# spotmicroservo.net
KiCad netlist of a schematic drawn in EAGLE
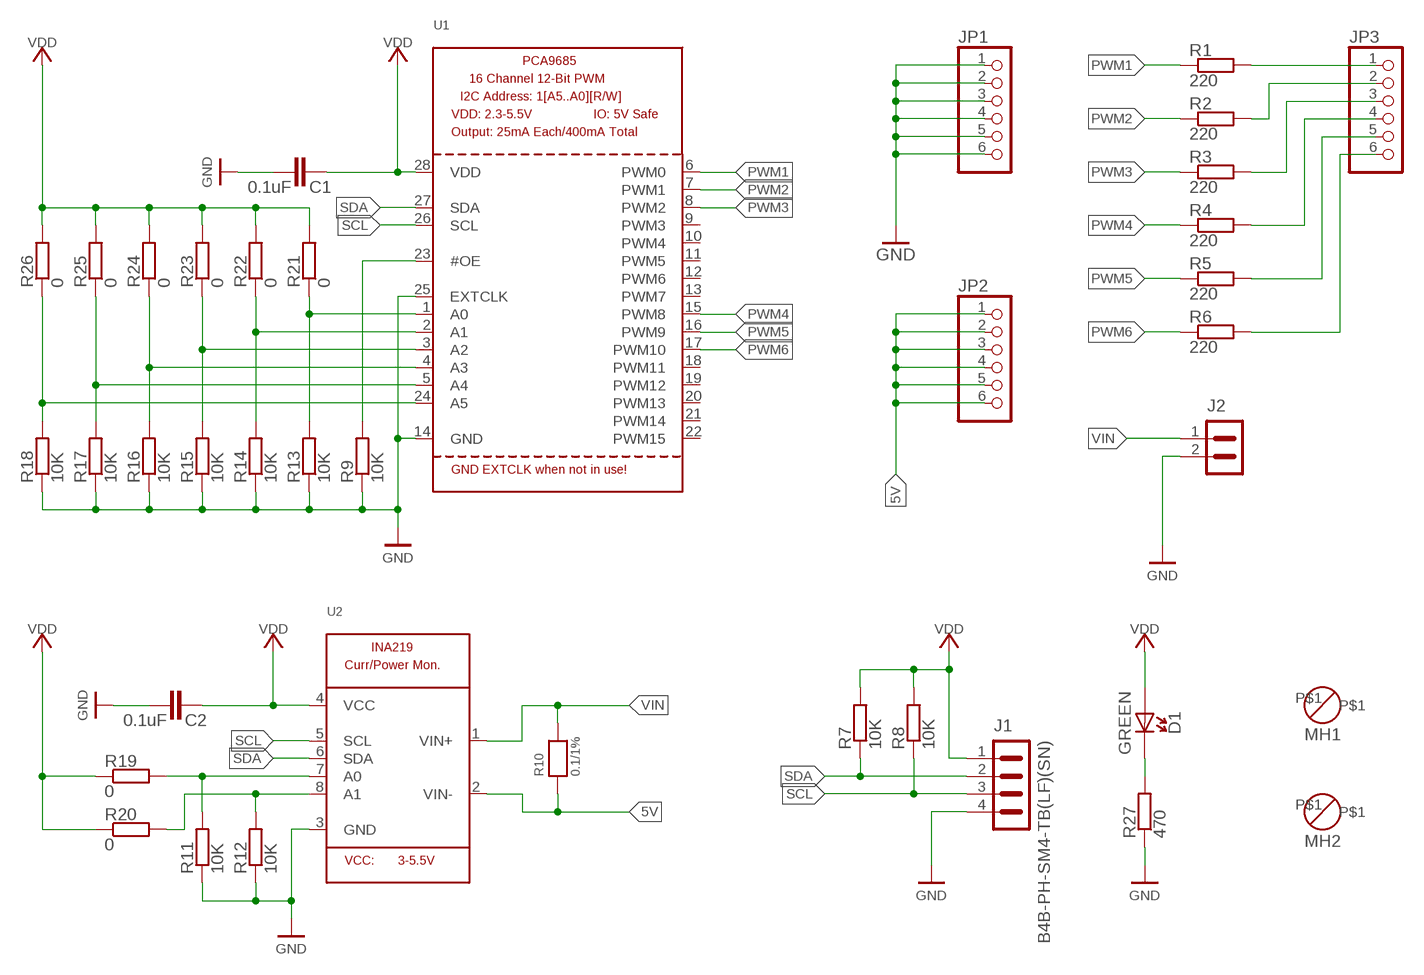
[diagram p0: schematic, sheet 1]

(export (version "E")
  (design (tool "Eeschema 10.0.6"))
  (components
    (comp (ref "C1")
      (value "0.1uF")
      (footprint "eagle-import:C0402")
      (libsource (lib "eagle-import") (part "CAPACITOR_NPOL-0402"))
    )
    (comp (ref "C2")
      (value "0.1uF")
      (footprint "eagle-import:C0402")
      (libsource (lib "eagle-import") (part "CAPACITOR_NPOL-0402"))
    )
    (comp (ref "D1")
      (value "GREEN")
      (footprint "eagle-import:D0402")
      (libsource (lib "eagle-import") (part "LED_SINGLE-0402"))
    )
    (comp (ref "J1")
      (value "B4B-PH-SM4-TB(LF)(SN)")
      (footprint "eagle-import:CON_JST_B4B-PH-SM4-TB(LF)(SN)")
      (libsource (lib "eagle-import") (part "CON_HEADER_1X04_JST_B4B-PH-SM4-TB(LF)(SN)"))
    )
    (comp (ref "J2")
      (value "CON_HEADER_1X02-B2B-XH-A(LF)(SN)")
      (footprint "eagle-import:JST_B2B-XH-A(LF)(SN)")
      (libsource (lib "eagle-import") (part "CON_HEADER_1X02-B2B-XH-A(LF)(SN)"))
    )
    (comp (ref "JP1")
      (value "PINHD-1X6B")
      (footprint "eagle-import:1X06-BIG")
      (libsource (lib "eagle-import") (part "PINHD-1X6B"))
    )
    (comp (ref "JP2")
      (value "PINHD-1X6B")
      (footprint "eagle-import:1X06-BIG")
      (libsource (lib "eagle-import") (part "PINHD-1X6B"))
    )
    (comp (ref "JP3")
      (value "PINHD-1X6B")
      (footprint "eagle-import:1X06-BIG")
      (libsource (lib "eagle-import") (part "PINHD-1X6B"))
    )
    (comp (ref "MH1")
      (value "MOUNT-HOLE2.6MM")
      (footprint "eagle-import:MOUNT-HOLE2.6")
      (libsource (lib "eagle-import") (part "MOUNT-HOLE2.6MM"))
    )
    (comp (ref "MH2")
      (value "MOUNT-HOLE2.6MM")
      (footprint "eagle-import:MOUNT-HOLE2.6")
      (libsource (lib "eagle-import") (part "MOUNT-HOLE2.6MM"))
    )
    (comp (ref "R1")
      (value "220")
      (footprint "eagle-import:R0402")
      (libsource (lib "eagle-import") (part "RESISTOR-0402"))
    )
    (comp (ref "R2")
      (value "220")
      (footprint "eagle-import:R0402")
      (libsource (lib "eagle-import") (part "RESISTOR-0402"))
    )
    (comp (ref "R3")
      (value "220")
      (footprint "eagle-import:R0402")
      (libsource (lib "eagle-import") (part "RESISTOR-0402"))
    )
    (comp (ref "R4")
      (value "220")
      (footprint "eagle-import:R0402")
      (libsource (lib "eagle-import") (part "RESISTOR-0402"))
    )
    (comp (ref "R5")
      (value "220")
      (footprint "eagle-import:R0402")
      (libsource (lib "eagle-import") (part "RESISTOR-0402"))
    )
    (comp (ref "R6")
      (value "220")
      (footprint "eagle-import:R0402")
      (libsource (lib "eagle-import") (part "RESISTOR-0402"))
    )
    (comp (ref "R7")
      (value "10K")
      (footprint "eagle-import:R0402")
      (libsource (lib "eagle-import") (part "RESISTOR-0402"))
    )
    (comp (ref "R8")
      (value "10K")
      (footprint "eagle-import:R0402")
      (libsource (lib "eagle-import") (part "RESISTOR-0402"))
    )
    (comp (ref "R9")
      (value "10K")
      (footprint "eagle-import:R0402")
      (libsource (lib "eagle-import") (part "RESISTOR-0402"))
    )
    (comp (ref "R10")
      (value "0.1/1%")
      (footprint "eagle-import:MICROBUILDER_2512")
      (libsource (lib "eagle-import") (part "MICROBUILDER_RESISTOR2512"))
    )
    (comp (ref "R11")
      (value "10K")
      (footprint "eagle-import:R0402")
      (libsource (lib "eagle-import") (part "RESISTOR-0402"))
    )
    (comp (ref "R12")
      (value "10K")
      (footprint "eagle-import:R0402")
      (libsource (lib "eagle-import") (part "RESISTOR-0402"))
    )
    (comp (ref "R13")
      (value "10K")
      (footprint "eagle-import:R0402")
      (libsource (lib "eagle-import") (part "RESISTOR-0402"))
    )
    (comp (ref "R14")
      (value "10K")
      (footprint "eagle-import:R0402")
      (libsource (lib "eagle-import") (part "RESISTOR-0402"))
    )
    (comp (ref "R15")
      (value "10K")
      (footprint "eagle-import:R0402")
      (libsource (lib "eagle-import") (part "RESISTOR-0402"))
    )
    (comp (ref "R16")
      (value "10K")
      (footprint "eagle-import:R0402")
      (libsource (lib "eagle-import") (part "RESISTOR-0402"))
    )
    (comp (ref "R17")
      (value "10K")
      (footprint "eagle-import:R0402")
      (libsource (lib "eagle-import") (part "RESISTOR-0402"))
    )
    (comp (ref "R18")
      (value "10K")
      (footprint "eagle-import:R0402")
      (libsource (lib "eagle-import") (part "RESISTOR-0402"))
    )
    (comp (ref "R19")
      (value "0")
      (footprint "eagle-import:R0402")
      (libsource (lib "eagle-import") (part "RESISTOR-0402"))
    )
    (comp (ref "R20")
      (value "0")
      (footprint "eagle-import:R0402")
      (libsource (lib "eagle-import") (part "RESISTOR-0402"))
    )
    (comp (ref "R21")
      (value "0")
      (footprint "eagle-import:R0402")
      (libsource (lib "eagle-import") (part "RESISTOR-0402"))
    )
    (comp (ref "R22")
      (value "0")
      (footprint "eagle-import:R0402")
      (libsource (lib "eagle-import") (part "RESISTOR-0402"))
    )
    (comp (ref "R23")
      (value "0")
      (footprint "eagle-import:R0402")
      (libsource (lib "eagle-import") (part "RESISTOR-0402"))
    )
    (comp (ref "R24")
      (value "0")
      (footprint "eagle-import:R0402")
      (libsource (lib "eagle-import") (part "RESISTOR-0402"))
    )
    (comp (ref "R25")
      (value "0")
      (footprint "eagle-import:R0402")
      (libsource (lib "eagle-import") (part "RESISTOR-0402"))
    )
    (comp (ref "R26")
      (value "0")
      (footprint "eagle-import:R0402")
      (libsource (lib "eagle-import") (part "RESISTOR-0402"))
    )
    (comp (ref "R27")
      (value "470")
      (footprint "eagle-import:R0402")
      (libsource (lib "eagle-import") (part "RESISTOR-0402"))
    )
    (comp (ref "U1")
      (value "PCA9685")
      (footprint "eagle-import:TSSOP28")
      (libsource (lib "eagle-import") (part "PCA9685"))
    )
    (comp (ref "U2")
      (value "MICROBUILDER_INA219")
      (footprint "eagle-import:MICROBUILDER_SOT23-8")
      (libsource (lib "eagle-import") (part "MICROBUILDER_INA219"))
    )
  )
  (nets
    (net (code "1") (name "5V") (class "Default")
      (node (ref "JP2") (pin "1") (pinfunction "1_1") (pintype "passive"))
      (node (ref "JP2") (pin "2") (pinfunction "2_2") (pintype "passive"))
      (node (ref "JP2") (pin "3") (pinfunction "3_3") (pintype "passive"))
      (node (ref "JP2") (pin "4") (pinfunction "4_4") (pintype "passive"))
      (node (ref "JP2") (pin "5") (pinfunction "5_5") (pintype "passive"))
      (node (ref "JP2") (pin "6") (pinfunction "6_6") (pintype "passive"))
      (node (ref "R10") (pin "1") (pinfunction "1_1") (pintype "passive"))
      (node (ref "U2") (pin "2") (pinfunction "VIN-_2") (pintype "bidirectional"))
    )
    (net (code "2") (name "GND") (class "Default")
      (node (ref "C1") (pin "1") (pinfunction "1_1") (pintype "passive"))
      (node (ref "C2") (pin "1") (pinfunction "1_1") (pintype "passive"))
      (node (ref "J1") (pin "4") (pinfunction "4_4") (pintype "bidirectional"))
      (node (ref "J2") (pin "2") (pinfunction "2_2") (pintype "passive"))
      (node (ref "JP1") (pin "1") (pinfunction "1_1") (pintype "passive"))
      (node (ref "JP1") (pin "2") (pinfunction "2_2") (pintype "passive"))
      (node (ref "JP1") (pin "3") (pinfunction "3_3") (pintype "passive"))
      (node (ref "JP1") (pin "4") (pinfunction "4_4") (pintype "passive"))
      (node (ref "JP1") (pin "5") (pinfunction "5_5") (pintype "passive"))
      (node (ref "JP1") (pin "6") (pinfunction "6_6") (pintype "passive"))
      (node (ref "R11") (pin "1") (pinfunction "1_1") (pintype "passive"))
      (node (ref "R12") (pin "1") (pinfunction "1_1") (pintype "passive"))
      (node (ref "R13") (pin "1") (pinfunction "1_1") (pintype "passive"))
      (node (ref "R14") (pin "1") (pinfunction "1_1") (pintype "passive"))
      (node (ref "R15") (pin "1") (pinfunction "1_1") (pintype "passive"))
      (node (ref "R16") (pin "1") (pinfunction "1_1") (pintype "passive"))
      (node (ref "R17") (pin "1") (pinfunction "1_1") (pintype "passive"))
      (node (ref "R18") (pin "1") (pinfunction "1_1") (pintype "passive"))
      (node (ref "R27") (pin "1") (pinfunction "1_1") (pintype "passive"))
      (node (ref "R9") (pin "1") (pinfunction "1_1") (pintype "passive"))
      (node (ref "U1") (pin "14") (pinfunction "GND_14") (pintype "power_in"))
      (node (ref "U1") (pin "25") (pinfunction "EXTCLK_25") (pintype "input"))
      (node (ref "U2") (pin "3") (pinfunction "GND_3") (pintype "bidirectional"))
    )
    (net (code "3") (name "Net-(D1-C)") (class "Default")
      (node (ref "D1") (pin "2") (pinfunction "C_2") (pintype "passive"))
      (node (ref "R27") (pin "2") (pinfunction "2_2") (pintype "passive"))
    )
    (net (code "4") (name "Net-(JP3-Pad1)") (class "Default")
      (node (ref "JP3") (pin "1") (pinfunction "1_1") (pintype "passive"))
      (node (ref "R1") (pin "2") (pinfunction "2_2") (pintype "passive"))
    )
    (net (code "5") (name "Net-(JP3-Pad2)") (class "Default")
      (node (ref "JP3") (pin "2") (pinfunction "2_2") (pintype "passive"))
      (node (ref "R2") (pin "2") (pinfunction "2_2") (pintype "passive"))
    )
    (net (code "6") (name "Net-(JP3-Pad3)") (class "Default")
      (node (ref "JP3") (pin "3") (pinfunction "3_3") (pintype "passive"))
      (node (ref "R3") (pin "2") (pinfunction "2_2") (pintype "passive"))
    )
    (net (code "7") (name "Net-(JP3-Pad4)") (class "Default")
      (node (ref "JP3") (pin "4") (pinfunction "4_4") (pintype "passive"))
      (node (ref "R4") (pin "2") (pinfunction "2_2") (pintype "passive"))
    )
    (net (code "8") (name "Net-(JP3-Pad5)") (class "Default")
      (node (ref "JP3") (pin "5") (pinfunction "5_5") (pintype "passive"))
      (node (ref "R5") (pin "2") (pinfunction "2_2") (pintype "passive"))
    )
    (net (code "9") (name "Net-(JP3-Pad6)") (class "Default")
      (node (ref "JP3") (pin "6") (pinfunction "6_6") (pintype "passive"))
      (node (ref "R6") (pin "2") (pinfunction "2_2") (pintype "passive"))
    )
    (net (code "10") (name "Net-(U1-#OE)") (class "Default")
      (node (ref "R9") (pin "2") (pinfunction "2_2") (pintype "passive"))
      (node (ref "U1") (pin "23") (pinfunction "#OE_23") (pintype "input"))
    )
    (net (code "11") (name "Net-(U1-A0)") (class "Default")
      (node (ref "R13") (pin "2") (pinfunction "2_2") (pintype "passive"))
      (node (ref "R21") (pin "1") (pinfunction "1_1") (pintype "passive"))
      (node (ref "U1") (pin "1") (pinfunction "A0_1") (pintype "bidirectional"))
    )
    (net (code "12") (name "Net-(U1-A1)") (class "Default")
      (node (ref "R14") (pin "2") (pinfunction "2_2") (pintype "passive"))
      (node (ref "R22") (pin "1") (pinfunction "1_1") (pintype "passive"))
      (node (ref "U1") (pin "2") (pinfunction "A1_2") (pintype "bidirectional"))
    )
    (net (code "13") (name "Net-(U1-A2)") (class "Default")
      (node (ref "R15") (pin "2") (pinfunction "2_2") (pintype "passive"))
      (node (ref "R23") (pin "1") (pinfunction "1_1") (pintype "passive"))
      (node (ref "U1") (pin "3") (pinfunction "A2_3") (pintype "bidirectional"))
    )
    (net (code "14") (name "Net-(U1-A3)") (class "Default")
      (node (ref "R16") (pin "2") (pinfunction "2_2") (pintype "passive"))
      (node (ref "R24") (pin "1") (pinfunction "1_1") (pintype "passive"))
      (node (ref "U1") (pin "4") (pinfunction "A3_4") (pintype "bidirectional"))
    )
    (net (code "15") (name "Net-(U1-A4)") (class "Default")
      (node (ref "R17") (pin "2") (pinfunction "2_2") (pintype "passive"))
      (node (ref "R25") (pin "1") (pinfunction "1_1") (pintype "passive"))
      (node (ref "U1") (pin "5") (pinfunction "A4_5") (pintype "bidirectional"))
    )
    (net (code "16") (name "Net-(U1-A5)") (class "Default")
      (node (ref "R18") (pin "2") (pinfunction "2_2") (pintype "passive"))
      (node (ref "R26") (pin "1") (pinfunction "1_1") (pintype "passive"))
      (node (ref "U1") (pin "24") (pinfunction "A5_24") (pintype "bidirectional"))
    )
    (net (code "17") (name "Net-(U2-A0)") (class "Default")
      (node (ref "R11") (pin "2") (pinfunction "2_2") (pintype "passive"))
      (node (ref "R19") (pin "2") (pinfunction "2_2") (pintype "passive"))
      (node (ref "U2") (pin "7") (pinfunction "A0_7") (pintype "bidirectional"))
    )
    (net (code "18") (name "Net-(U2-A1)") (class "Default")
      (node (ref "R12") (pin "2") (pinfunction "2_2") (pintype "passive"))
      (node (ref "R20") (pin "2") (pinfunction "2_2") (pintype "passive"))
      (node (ref "U2") (pin "8") (pinfunction "A1_8") (pintype "bidirectional"))
    )
    (net (code "19") (name "PWM1") (class "Default")
      (node (ref "R1") (pin "1") (pinfunction "1_1") (pintype "passive"))
      (node (ref "U1") (pin "6") (pinfunction "PWM0_6") (pintype "output"))
    )
    (net (code "20") (name "PWM2") (class "Default")
      (node (ref "R2") (pin "1") (pinfunction "1_1") (pintype "passive"))
      (node (ref "U1") (pin "7") (pinfunction "PWM1_7") (pintype "output"))
    )
    (net (code "21") (name "PWM3") (class "Default")
      (node (ref "R3") (pin "1") (pinfunction "1_1") (pintype "passive"))
      (node (ref "U1") (pin "8") (pinfunction "PWM2_8") (pintype "output"))
    )
    (net (code "22") (name "PWM4") (class "Default")
      (node (ref "R4") (pin "1") (pinfunction "1_1") (pintype "passive"))
      (node (ref "U1") (pin "15") (pinfunction "PWM8_15") (pintype "output"))
    )
    (net (code "23") (name "PWM5") (class "Default")
      (node (ref "R5") (pin "1") (pinfunction "1_1") (pintype "passive"))
      (node (ref "U1") (pin "16") (pinfunction "PWM9_16") (pintype "output"))
    )
    (net (code "24") (name "PWM6") (class "Default")
      (node (ref "R6") (pin "1") (pinfunction "1_1") (pintype "passive"))
      (node (ref "U1") (pin "17") (pinfunction "PWM10_17") (pintype "output"))
    )
    (net (code "25") (name "SCL") (class "Default")
      (node (ref "J1") (pin "3") (pinfunction "3_3") (pintype "bidirectional"))
      (node (ref "R8") (pin "1") (pinfunction "1_1") (pintype "passive"))
      (node (ref "U1") (pin "26") (pinfunction "SCL_26") (pintype "bidirectional"))
      (node (ref "U2") (pin "5") (pinfunction "SCL_5") (pintype "bidirectional"))
    )
    (net (code "26") (name "SDA") (class "Default")
      (node (ref "J1") (pin "2") (pinfunction "2_2") (pintype "bidirectional"))
      (node (ref "R7") (pin "1") (pinfunction "1_1") (pintype "passive"))
      (node (ref "U1") (pin "27") (pinfunction "SDA_27") (pintype "bidirectional"))
      (node (ref "U2") (pin "6") (pinfunction "SDA_6") (pintype "bidirectional"))
    )
    (net (code "27") (name "VDD") (class "Default")
      (node (ref "C1") (pin "2") (pinfunction "2_2") (pintype "passive"))
      (node (ref "C2") (pin "2") (pinfunction "2_2") (pintype "passive"))
      (node (ref "D1") (pin "1") (pinfunction "A_1") (pintype "passive"))
      (node (ref "J1") (pin "1") (pinfunction "1_1") (pintype "bidirectional"))
      (node (ref "R19") (pin "1") (pinfunction "1_1") (pintype "passive"))
      (node (ref "R20") (pin "1") (pinfunction "1_1") (pintype "passive"))
      (node (ref "R21") (pin "2") (pinfunction "2_2") (pintype "passive"))
      (node (ref "R22") (pin "2") (pinfunction "2_2") (pintype "passive"))
      (node (ref "R23") (pin "2") (pinfunction "2_2") (pintype "passive"))
      (node (ref "R24") (pin "2") (pinfunction "2_2") (pintype "passive"))
      (node (ref "R25") (pin "2") (pinfunction "2_2") (pintype "passive"))
      (node (ref "R26") (pin "2") (pinfunction "2_2") (pintype "passive"))
      (node (ref "R7") (pin "2") (pinfunction "2_2") (pintype "passive"))
      (node (ref "R8") (pin "2") (pinfunction "2_2") (pintype "passive"))
      (node (ref "U1") (pin "28") (pinfunction "VDD_28") (pintype "power_in"))
      (node (ref "U2") (pin "4") (pinfunction "VCC_4") (pintype "bidirectional"))
    )
    (net (code "28") (name "VIN") (class "Default")
      (node (ref "J2") (pin "1") (pinfunction "1_1") (pintype "passive"))
      (node (ref "R10") (pin "2") (pinfunction "2_2") (pintype "passive"))
      (node (ref "U2") (pin "1") (pinfunction "VIN+_1") (pintype "bidirectional"))
    )
    (net (code "29") (name "unconnected-(MH1-PadP$1)") (class "Default")
      (node (ref "MH1") (pin "P$1") (pinfunction "P$1_P$1") (pintype "passive"))
    )
    (net (code "30") (name "unconnected-(MH2-PadP$1)") (class "Default")
      (node (ref "MH2") (pin "P$1") (pinfunction "P$1_P$1") (pintype "passive"))
    )
    (net (code "31") (name "unconnected-(U1-PWM3-Pad9)") (class "Default")
      (node (ref "U1") (pin "9") (pinfunction "PWM3_9") (pintype "output"))
    )
    (net (code "32") (name "unconnected-(U1-PWM4-Pad10)") (class "Default")
      (node (ref "U1") (pin "10") (pinfunction "PWM4_10") (pintype "output"))
    )
    (net (code "33") (name "unconnected-(U1-PWM5-Pad11)") (class "Default")
      (node (ref "U1") (pin "11") (pinfunction "PWM5_11") (pintype "output"))
    )
    (net (code "34") (name "unconnected-(U1-PWM6-Pad12)") (class "Default")
      (node (ref "U1") (pin "12") (pinfunction "PWM6_12") (pintype "output"))
    )
    (net (code "35") (name "unconnected-(U1-PWM7-Pad13)") (class "Default")
      (node (ref "U1") (pin "13") (pinfunction "PWM7_13") (pintype "output"))
    )
    (net (code "36") (name "unconnected-(U1-PWM11-Pad18)") (class "Default")
      (node (ref "U1") (pin "18") (pinfunction "PWM11_18") (pintype "output"))
    )
    (net (code "37") (name "unconnected-(U1-PWM12-Pad19)") (class "Default")
      (node (ref "U1") (pin "19") (pinfunction "PWM12_19") (pintype "output"))
    )
    (net (code "38") (name "unconnected-(U1-PWM13-Pad20)") (class "Default")
      (node (ref "U1") (pin "20") (pinfunction "PWM13_20") (pintype "output"))
    )
    (net (code "39") (name "unconnected-(U1-PWM14-Pad21)") (class "Default")
      (node (ref "U1") (pin "21") (pinfunction "PWM14_21") (pintype "output"))
    )
    (net (code "40") (name "unconnected-(U1-PWM15-Pad22)") (class "Default")
      (node (ref "U1") (pin "22") (pinfunction "PWM15_22") (pintype "output"))
    )
  )
)
